# NNP-DWG-125-001-000_PG4_Schematic_Drawin.net
KiCad netlist of a schematic drawn in Altium Designer
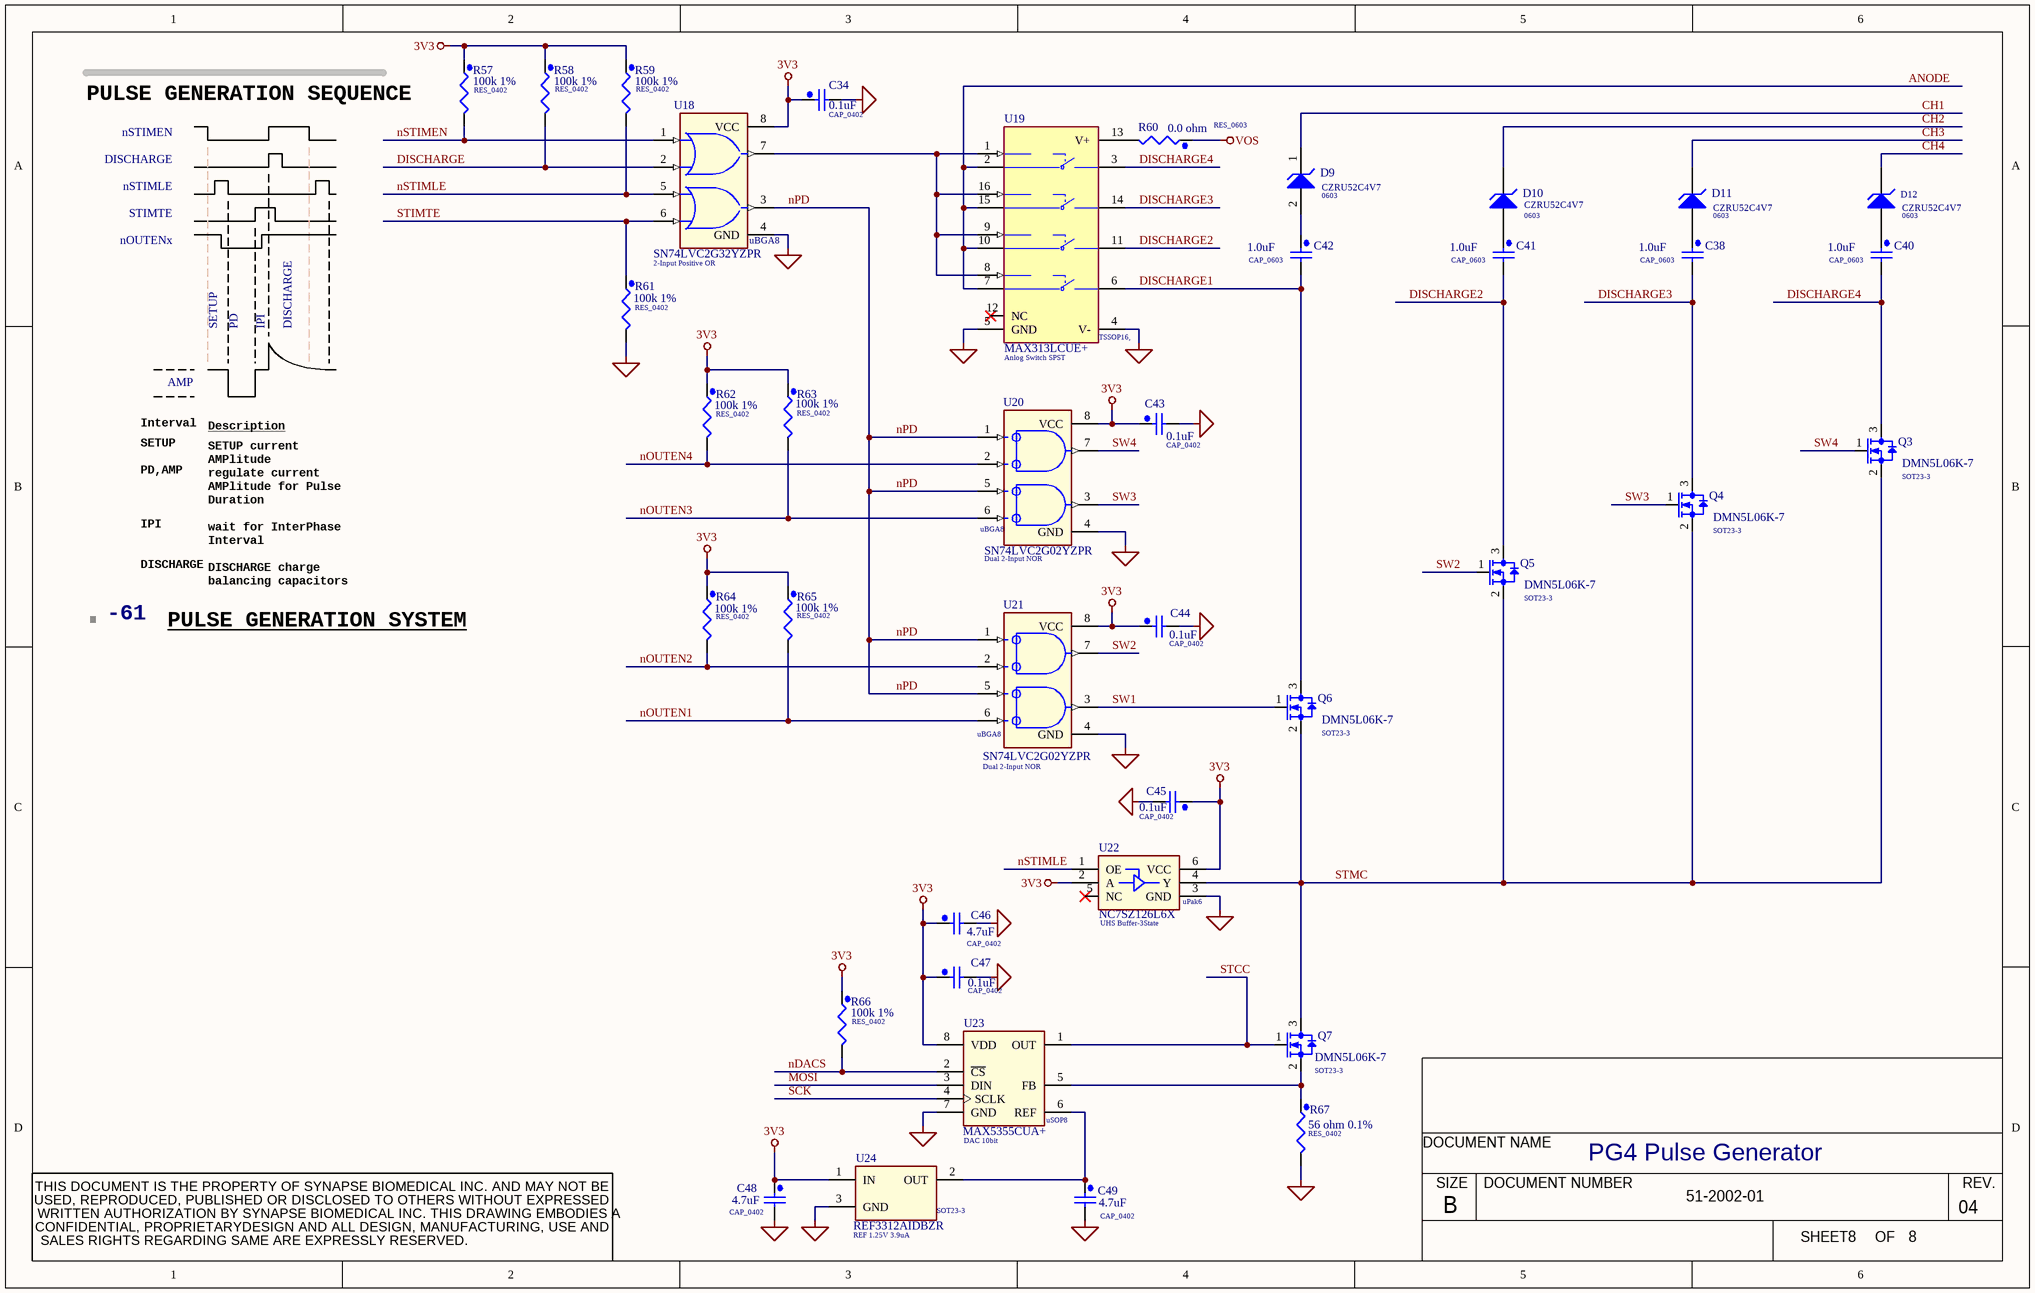
[diagram p0: NNP-DWG-125-001-000 PG4 Schematic Drawing Pg8.SchDoc]

(export (version "E")
  (design (tool "Eeschema 10.0.6"))
  (components
    (comp (ref "-61")
      (value "BOM_S1")
      (description "BOM item small graphic")
      (fields (field (name "XDESCRIPTION") "PULSE GENERATION SYSTEM"))
      (libsource (lib "BOM_sym") (part "BOM_S1"))
    )
    (comp (ref "C34")
      (value "0.1uF")
      (footprint "CAP_0402")
      (description "0.1uF, 16V, X7R, 0402, RoHS")
      (fields
        (field (name "MFR") "Murata Electronics North America")
        (field (name "PACKAGEDESCRIPTION") "CAP_0402")
        (field (name "MPN") "GRM155R71C104KA88D")
      )
      (libsource (lib "NNPS Integrated Parts") (part "GRM155R71C104KA88D"))
    )
    (comp (ref "C38")
      (value "1.0uF")
      (footprint "CAP_0603")
      (description "1uF, 50V, X5R, 10%, 0603, RoHS")
      (fields
        (field (name "MFR") "Murata Electronics North America")
        (field (name "PACKAGEDESCRIPTION") "CAP_0603")
        (field (name "MPN") "GRM188R61H105KAALD")
      )
      (libsource (lib "NNPS Integrated Parts") (part "UMK107BJ105KA-T"))
    )
    (comp (ref "C40")
      (value "1.0uF")
      (footprint "CAP_0603")
      (description "1uF, 50V, X5R, 10%, 0603, RoHS")
      (fields
        (field (name "MFR") "Murata Electronics North America")
        (field (name "PACKAGEDESCRIPTION") "CAP_0603")
        (field (name "MPN") "GRM188R61H105KAALD")
      )
      (libsource (lib "NNPS Integrated Parts") (part "UMK107BJ105KA-T"))
    )
    (comp (ref "C41")
      (value "1.0uF")
      (footprint "CAP_0603")
      (description "1uF, 50V, X5R, 10%, 0603, RoHS")
      (fields
        (field (name "MFR") "Murata Electronics North America")
        (field (name "PACKAGEDESCRIPTION") "CAP_0603")
        (field (name "MPN") "GRM188R61H105KAALD")
      )
      (libsource (lib "NNPS Integrated Parts") (part "UMK107BJ105KA-T"))
    )
    (comp (ref "C42")
      (value "1.0uF")
      (footprint "CAP_0603")
      (description "1uF, 50V, X5R, 10%, 0603, RoHS")
      (fields
        (field (name "MFR") "Murata Electronics North America")
        (field (name "PACKAGEDESCRIPTION") "CAP_0603")
        (field (name "MPN") "GRM188R61H105KAALD")
      )
      (libsource (lib "NNPS Integrated Parts") (part "UMK107BJ105KA-T"))
    )
    (comp (ref "C43")
      (value "0.1uF")
      (footprint "CAP_0402")
      (description "0.1uF, 16V, X7R, 0402, RoHS")
      (fields
        (field (name "MFR") "Murata Electronics North America")
        (field (name "PACKAGEDESCRIPTION") "CAP_0402")
        (field (name "MPN") "GRM155R71C104KA88D")
      )
      (libsource (lib "NNPS Integrated Parts") (part "GRM155R71C104KA88D"))
    )
    (comp (ref "C44")
      (value "0.1uF")
      (footprint "CAP_0402")
      (description "0.1uF, 16V, X7R, 0402, RoHS")
      (fields
        (field (name "MFR") "Murata Electronics North America")
        (field (name "PACKAGEDESCRIPTION") "CAP_0402")
        (field (name "MPN") "GRM155R71C104KA88D")
      )
      (libsource (lib "NNPS Integrated Parts") (part "GRM155R71C104KA88D"))
    )
    (comp (ref "C45")
      (value "0.1uF")
      (footprint "CAP_0402")
      (description "0.1uF, 16V, X7R, 0402, RoHS")
      (fields
        (field (name "MFR") "Murata Electronics North America")
        (field (name "PACKAGEDESCRIPTION") "CAP_0402")
        (field (name "MPN") "GRM155R71C104KA88D")
      )
      (libsource (lib "NNPS Integrated Parts") (part "GRM155R71C104KA88D"))
    )
    (comp (ref "C46")
      (value "4.7uF")
      (footprint "CAP_0402")
      (description "4.7uF, 6.3V, X5R, 20%, 0402, RoHS")
      (fields
        (field (name "MFR") "Murata Electronics North America")
        (field (name "PACKAGEDESCRIPTION") "CAP_0402")
        (field (name "MPN") "GRM155R60J475ME47D")
      )
      (libsource (lib "NNPS Integrated Parts") (part "ECJ-0EB0J475M"))
    )
    (comp (ref "C47")
      (value "0.1uF")
      (footprint "CAP_0402")
      (description "0.1uF, 16V, X7R, 0402, RoHS")
      (fields
        (field (name "MFR") "Murata Electronics North America")
        (field (name "PACKAGEDESCRIPTION") "CAP_0402")
        (field (name "MPN") "GRM155R71C104KA88D")
      )
      (libsource (lib "NNPS Integrated Parts") (part "GRM155R71C104KA88D"))
    )
    (comp (ref "C48")
      (value "4.7uF")
      (footprint "CAP_0402")
      (description "4.7uF, 6.3V, X5R, 20%, 0402, RoHS")
      (fields
        (field (name "MFR") "Murata Electronics North America")
        (field (name "PACKAGEDESCRIPTION") "CAP_0402")
        (field (name "MPN") "GRM155R60J475ME47D")
      )
      (libsource (lib "NNPS Integrated Parts") (part "ECJ-0EB0J475M"))
    )
    (comp (ref "C49")
      (value "4.7uF")
      (footprint "CAP_0402")
      (description "4.7uF, 6.3V, X5R, 20%, 0402, RoHS")
      (fields
        (field (name "MFR") "Murata Electronics North America")
        (field (name "PACKAGEDESCRIPTION") "CAP_0402")
        (field (name "MPN") "GRM155R60J475ME47D")
      )
      (libsource (lib "NNPS Integrated Parts") (part "ECJ-0EB0J475M"))
    )
    (comp (ref "D9")
      (value "Zener Diode, 15V, 150mW, 0603, RoHS")
      (footprint "DIODES_SOD-523FL")
      (description "Zener Diode, 4.7V, 150 mW, 0603, RoHS")
      (fields
        (field (name "MFR") "Comchip Technology")
        (field (name "PACKAGEDESCRIPTION") "0603")
        (field (name "MPN") "CZRU52C4V7")
      )
      (libsource (lib "Simulation Sources") (part "DFLZ15-7"))
    )
    (comp (ref "D10")
      (value "Zener Diode, 15V, 150mW, 0603, RoHS")
      (footprint "B0-0000-85-8 Rev 006-a Altium Source for PCB:DIODES_SOD-523FL")
      (description "Zener Diode, 4.7V, 150 mW, 0603, RoHS")
      (fields
        (field (name "MFR") "Comchip Technology")
        (field (name "PACKAGEDESCRIPTION") "0603")
        (field (name "MPN") "CZRU52C4V7")
      )
      (libsource (lib "NNPS Integrated Parts") (part "DFLZ15-7"))
    )
    (comp (ref "D11")
      (value "Zener Diode, 15V, 150mW, 0603, RoHS")
      (footprint "DIODES_SOD-523FL")
      (description "Zener Diode, 4.7V, 150 mW, 0603, RoHS")
      (fields
        (field (name "MFR") "Comchip Technology")
        (field (name "PACKAGEDESCRIPTION") "0603")
        (field (name "MPN") "CZRU52C4V7")
      )
      (libsource (lib "NNPS Integrated Parts") (part "DFLZ15-7"))
    )
    (comp (ref "D12")
      (value "Zener Diode, 15V, 150mW, 0603, RoHS")
      (footprint "DIODES_SOD-523FL")
      (description "Zener Diode, 4.7V, 150 mW, 0603, RoHS")
      (fields
        (field (name "MFR") "Comchip Technology")
        (field (name "PACKAGEDESCRIPTION") "0603")
        (field (name "MPN") "CZRU52C4V7")
      )
      (libsource (lib "NNPS Integrated Parts") (part "DFLZ15-7"))
    )
    (comp (ref "Q3")
      (value "DMN5L06K-7")
      (footprint "SOT23-3")
      (description "N-Channel MOSFET, 50V, 300mA, SOT23, RoHS")
      (fields
        (field (name "MFR") "Diodes Incorporated")
        (field (name "PACKAGEDESCRIPTION") "SOT23-3")
        (field (name "Comment") "M_50_300m_SOT23")
      )
      (libsource (lib "NNPS Integrated Parts") (part "DMN5L06K-7"))
    )
    (comp (ref "Q4")
      (value "DMN5L06K-7")
      (footprint "SOT23-3")
      (description "N-Channel MOSFET, 50V, 300mA, SOT23, RoHS")
      (fields
        (field (name "MFR") "Diodes Incorporated")
        (field (name "PACKAGEDESCRIPTION") "SOT23-3")
        (field (name "Comment") "M_50_300m_SOT23")
      )
      (libsource (lib "NNPS Integrated Parts") (part "DMN5L06K-7"))
    )
    (comp (ref "Q5")
      (value "DMN5L06K-7")
      (footprint "SOT23-3")
      (description "N-Channel MOSFET, 50V, 300mA, SOT23, RoHS")
      (fields
        (field (name "MFR") "Diodes Incorporated")
        (field (name "PACKAGEDESCRIPTION") "SOT23-3")
        (field (name "Comment") "M_50_300m_SOT23")
      )
      (libsource (lib "NNPS Integrated Parts") (part "DMN5L06K-7"))
    )
    (comp (ref "Q6")
      (value "DMN5L06K-7")
      (footprint "SOT23-3")
      (description "N-Channel MOSFET, 50V, 300mA, SOT23, RoHS")
      (fields
        (field (name "MFR") "Diodes Incorporated")
        (field (name "PACKAGEDESCRIPTION") "SOT23-3")
        (field (name "Comment") "M_50_300m_SOT23")
      )
      (libsource (lib "NNPS Integrated Parts") (part "DMN5L06K-7"))
    )
    (comp (ref "Q7")
      (value "DMN5L06K-7")
      (footprint "SOT23-3")
      (description "N-Channel MOSFET, 50V, 300mA, SOT23, RoHS")
      (fields
        (field (name "MFR") "Diodes Incorporated")
        (field (name "PACKAGEDESCRIPTION") "SOT23-3")
        (field (name "Comment") "M_50_300m_SOT23")
      )
      (libsource (lib "NNPS Integrated Parts") (part "DMN5L06K-7"))
    )
    (comp (ref "R57")
      (value "100k 1%")
      (footprint "RES_0402")
      (description "100k ohm, 1%, 1/16W, smd, 0402, RoHS")
      (fields
        (field (name "MFR") "Vishay Dale")
        (field (name "PACKAGEDESCRIPTION") "RES_0402")
        (field (name "MPN") "CRCW04025K10FKED")
      )
      (libsource (lib "NNPS Integrated Parts") (part "MCR01MZPF1003"))
    )
    (comp (ref "R58")
      (value "100k 1%")
      (footprint "RES_0402")
      (description "100k ohm, 1%, 1/16W, smd, 0402, RoHS")
      (fields
        (field (name "MFR") "Vishay Dale")
        (field (name "PACKAGEDESCRIPTION") "RES_0402")
        (field (name "MPN") "CRCW04025K10FKED")
      )
      (libsource (lib "NNPS Integrated Parts") (part "MCR01MZPF1003"))
    )
    (comp (ref "R59")
      (value "100k 1%")
      (footprint "RES_0402")
      (description "100k ohm, 1%, 1/16W, smd, 0402, RoHS")
      (fields
        (field (name "MFR") "Vishay Dale")
        (field (name "PACKAGEDESCRIPTION") "RES_0402")
        (field (name "MPN") "CRCW04025K10FKED")
      )
      (libsource (lib "NNPS Integrated Parts") (part "MCR01MZPF1003"))
    )
    (comp (ref "R60")
      (value "0.0 ohm")
      (footprint "RES_0603")
      (description "0.0 ohm, 1/10W, 0603, RoHS")
      (fields
        (field (name "MFR") "Vishay Dale")
        (field (name "PACKAGEDESCRIPTION") "RES_0603")
        (field (name "MPN") "MCR03ERTJ000")
      )
      (libsource (lib "NNPS Integrated Parts") (part "MCR03ERTJ000"))
    )
    (comp (ref "R61")
      (value "100k 1%")
      (footprint "RES_0402")
      (description "100k ohm, 1%, 1/16W, smd, 0402, RoHS")
      (fields
        (field (name "MFR") "Vishay Dale")
        (field (name "PACKAGEDESCRIPTION") "RES_0402")
        (field (name "MPN") "CRCW04025K10FKED")
      )
      (libsource (lib "NNPS Integrated Parts") (part "MCR01MZPF1003"))
    )
    (comp (ref "R62")
      (value "100k 1%")
      (footprint "RES_0402")
      (description "100k ohm, 1%, 1/16W, smd, 0402, RoHS")
      (fields
        (field (name "MFR") "Vishay Dale")
        (field (name "PACKAGEDESCRIPTION") "RES_0402")
        (field (name "MPN") "CRCW04025K10FKED")
      )
      (libsource (lib "NNPS Integrated Parts") (part "MCR01MZPF1003"))
    )
    (comp (ref "R63")
      (value "100k 1%")
      (footprint "RES_0402")
      (description "100k ohm, 1%, 1/16W, smd, 0402, RoHS")
      (fields
        (field (name "MFR") "Vishay Dale")
        (field (name "PACKAGEDESCRIPTION") "RES_0402")
        (field (name "MPN") "CRCW04025K10FKED")
      )
      (libsource (lib "NNPS Integrated Parts") (part "MCR01MZPF1003"))
    )
    (comp (ref "R64")
      (value "100k 1%")
      (footprint "RES_0402")
      (description "100k ohm, 1%, 1/16W, smd, 0402, RoHS")
      (fields
        (field (name "MFR") "Vishay Dale")
        (field (name "PACKAGEDESCRIPTION") "RES_0402")
        (field (name "MPN") "CRCW04025K10FKED")
      )
      (libsource (lib "NNPS Integrated Parts") (part "MCR01MZPF1003"))
    )
    (comp (ref "R65")
      (value "100k 1%")
      (footprint "RES_0402")
      (description "100k ohm, 1%, 1/16W, smd, 0402, RoHS")
      (fields
        (field (name "MFR") "Vishay Dale")
        (field (name "PACKAGEDESCRIPTION") "RES_0402")
        (field (name "MPN") "CRCW04025K10FKED")
      )
      (libsource (lib "NNPS Integrated Parts") (part "MCR01MZPF1003"))
    )
    (comp (ref "R66")
      (value "100k 1%")
      (footprint "RES_0402")
      (description "100k ohm, 1%, 1/16W, smd, 0402, RoHS")
      (fields
        (field (name "MFR") "Vishay Dale")
        (field (name "PACKAGEDESCRIPTION") "RES_0402")
        (field (name "MPN") "CRCW04025K10FKED")
      )
      (libsource (lib "NNPS Integrated Parts") (part "MCR01MZPF1003"))
    )
    (comp (ref "R67")
      (value "56 ohm 0.1%")
      (footprint "RES_0402")
      (description "56 ohm, 0.1%, 1/16W, 0402, RoHS")
      (fields
        (field (name "MFR") "Vishay Dale")
        (field (name "PACKAGEDESCRIPTION") "RES_0402")
        (field (name "MPN") "CRCW040256R0FKED")
      )
      (libsource (lib "NNPS Integrated Parts") (part "RG1005P-560-B-T5"))
    )
    (comp (ref "U18")
      (value "2-Input Positive OR")
      (footprint "DSBGA-8-YZP")
      (description "2-Input Positive OR, 1.65-5.5V,  uBGA8, RoHS")
      (fields
        (field (name "MFR") "Texas Instruments")
        (field (name "PACKAGEDESCRIPTION") "uBGA8")
        (field (name "MPN") "SN74LVC2G32YZPR")
      )
      (libsource (lib "NNPS Integrated Parts") (part "SN74LVC2G32YEA"))
    )
    (comp (ref "U19")
      (value "Anlog Switch SPST")
      (footprint "TSSOP16")
      (description "Analog Switch, 10ohm, QUAD SPST, TSSOP16, RoHS")
      (fields
        (field (name "PACKAGEDESCRIPTION") "TSSOP16,")
        (field (name "MFR") "Maxim Integrated")
        (field (name "MPN") "MAX313LCUE+")
      )
      (libsource (lib "NNPS Integrated Parts") (part "MAX313LCUE"))
    )
    (comp (ref "U20")
      (value "Dual 2-Input NOR")
      (footprint "DSBGA-8-YZP")
      (description "Dual 2-Input NOR, 1.65-5.5V, uBGA8, RoHS")
      (fields
        (field (name "MFR") "Texas Instruments")
        (field (name "PACKAGEDESCRIPTION") "uBGA8")
        (field (name "MPN") "SN74LVC2G02YZPR")
      )
      (libsource (lib "NNPS Integrated Parts") (part "SN74LVC2G02YEA"))
    )
    (comp (ref "U21")
      (value "Dual 2-Input NOR")
      (footprint "DSBGA-8-YZP")
      (description "Dual 2-Input NOR, 1.65-5.5V, uBGA8, RoHS")
      (fields
        (field (name "MFR") "Texas Instruments")
        (field (name "PACKAGEDESCRIPTION") "uBGA8")
        (field (name "MPN") "SN74LVC2G02YZPR")
      )
      (libsource (lib "NNPS Integrated Parts") (part "SN74LVC2G02YEA"))
    )
    (comp (ref "U22")
      (value "UHS Buffer-3State")
      (footprint "uPak6")
      (description "UHS Buffer Tri-State, uPAK6, RoHS")
      (fields
        (field (name "MFR") "Fairchild Semiconductor")
        (field (name "PACKAGEDESCRIPTION") "uPak6")
        (field (name "MPN") "NC7SZ126L6X")
      )
      (libsource (lib "NNPS Integrated Parts") (part "NC7SZ126L6X"))
    )
    (comp (ref "U23")
      (value "DAC 10bit")
      (footprint "uSOP-8L")
      (description "DAC 10bit, uSOP8, RoHS")
      (fields
        (field (name "PACKAGEDESCRIPTION") "uSOP8")
        (field (name "MFR") "Maxim Integrated")
        (field (name "MPN") "MAX5355CUA+")
      )
      (libsource (lib "NNPS Integrated Parts") (part "MAX5355CUA+"))
    )
    (comp (ref "U24")
      (value "REF 1.25V 3.9uA")
      (footprint "SOT23-3")
      (description "REF 1.25V, 3.9uA, SOT23-3, RoHS")
      (fields
        (field (name "PACKAGEDESCRIPTION") "SOT23-3")
        (field (name "MFR") "Texas Instruments")
        (field (name "MPN") "REF3312AIDBZR")
      )
      (libsource (lib "NNPS Integrated Parts") (part "REF3312AIDCK"))
    )
  )
  (nets
    (net (code "1") (name "/ANODE") (class "Default")
      (node (ref "U19") (pin "10") (pinfunction "COM3_10") (pintype "passive"))
      (node (ref "U19") (pin "15") (pinfunction "COM2_15") (pintype "passive"))
      (node (ref "U19") (pin "2") (pinfunction "COM1_2") (pintype "passive"))
      (node (ref "U19") (pin "7") (pinfunction "COM4_7") (pintype "passive"))
    )
    (net (code "2") (name "/CH1") (class "Default")
      (node (ref "D9") (pin "1") (pinfunction "1_1") (pintype "passive"))
    )
    (net (code "3") (name "/CH2") (class "Default")
      (node (ref "D10") (pin "1") (pinfunction "C_1") (pintype "passive"))
    )
    (net (code "4") (name "/CH3") (class "Default")
      (node (ref "D11") (pin "1") (pinfunction "C_1") (pintype "passive"))
    )
    (net (code "5") (name "/CH4") (class "Default")
      (node (ref "D12") (pin "1") (pinfunction "C_1") (pintype "passive"))
    )
    (net (code "6") (name "/DISCHARGE") (class "Default")
      (node (ref "R58") (pin "2") (pinfunction "2_2") (pintype "passive"))
      (node (ref "U18") (pin "2") (pinfunction "1B_2") (pintype "input"))
    )
    (net (code "7") (name "/DISCHARGE1") (class "Default")
      (node (ref "C42") (pin "2") (pinfunction "2_2") (pintype "passive"))
      (node (ref "Q6") (pin "3") (pinfunction "D_3") (pintype "passive"))
      (node (ref "U19") (pin "6") (pinfunction "NO4_6") (pintype "passive"))
    )
    (net (code "8") (name "/DISCHARGE2") (class "Default")
      (node (ref "C41") (pin "2") (pinfunction "2_2") (pintype "passive"))
      (node (ref "Q5") (pin "3") (pinfunction "D_3") (pintype "passive"))
      (node (ref "U19") (pin "11") (pinfunction "NO3_11") (pintype "passive"))
    )
    (net (code "9") (name "/DISCHARGE3") (class "Default")
      (node (ref "C38") (pin "2") (pinfunction "2_2") (pintype "passive"))
      (node (ref "Q4") (pin "3") (pinfunction "D_3") (pintype "passive"))
      (node (ref "U19") (pin "14") (pinfunction "NO2_14") (pintype "passive"))
    )
    (net (code "10") (name "/DISCHARGE4") (class "Default")
      (node (ref "C40") (pin "2") (pinfunction "2_2") (pintype "passive"))
      (node (ref "Q3") (pin "3") (pinfunction "D_3") (pintype "passive"))
      (node (ref "U19") (pin "3") (pinfunction "NO1_3") (pintype "passive"))
    )
    (net (code "11") (name "/MOSI") (class "Default")
      (node (ref "U23") (pin "3") (pinfunction "DIN_3") (pintype "passive"))
    )
    (net (code "12") (name "/SCK") (class "Default")
      (node (ref "U23") (pin "4") (pinfunction "SCLK_4") (pintype "passive"))
    )
    (net (code "13") (name "/STCC") (class "Default")
      (node (ref "Q7") (pin "1") (pinfunction "G_1") (pintype "passive"))
      (node (ref "U23") (pin "1") (pinfunction "OUT_1") (pintype "passive"))
    )
    (net (code "14") (name "/STIMTE") (class "Default")
      (node (ref "R61") (pin "1") (pinfunction "1_1") (pintype "passive"))
      (node (ref "U18") (pin "6") (pinfunction "2B_6") (pintype "input"))
    )
    (net (code "15") (name "/STMC") (class "Default")
      (node (ref "Q3") (pin "2") (pinfunction "S_2") (pintype "passive"))
      (node (ref "Q4") (pin "2") (pinfunction "S_2") (pintype "passive"))
      (node (ref "Q5") (pin "2") (pinfunction "S_2") (pintype "passive"))
      (node (ref "Q6") (pin "2") (pinfunction "S_2") (pintype "passive"))
      (node (ref "Q7") (pin "3") (pinfunction "D_3") (pintype "passive"))
      (node (ref "U22") (pin "4") (pinfunction "Y_4") (pintype "passive"))
    )
    (net (code "16") (name "/SW1") (class "Default")
      (node (ref "Q6") (pin "1") (pinfunction "G_1") (pintype "passive"))
      (node (ref "U21") (pin "3") (pinfunction "2Y_3") (pintype "output"))
    )
    (net (code "17") (name "/SW2") (class "Default")
      (node (ref "Q5") (pin "1") (pinfunction "G_1") (pintype "passive"))
      (node (ref "U21") (pin "7") (pinfunction "Y_7") (pintype "output"))
    )
    (net (code "18") (name "/SW3") (class "Default")
      (node (ref "Q4") (pin "1") (pinfunction "G_1") (pintype "passive"))
      (node (ref "U20") (pin "3") (pinfunction "2Y_3") (pintype "output"))
    )
    (net (code "19") (name "/SW4") (class "Default")
      (node (ref "Q3") (pin "1") (pinfunction "G_1") (pintype "passive"))
      (node (ref "U20") (pin "7") (pinfunction "Y_7") (pintype "output"))
    )
    (net (code "20") (name "/nDACS") (class "Default")
      (node (ref "R66") (pin "2") (pinfunction "2_2") (pintype "passive"))
      (node (ref "U23") (pin "2") (pinfunction "~{CS}_2") (pintype "passive"))
    )
    (net (code "21") (name "/nOUTEN1") (class "Default")
      (node (ref "R65") (pin "2") (pinfunction "2_2") (pintype "passive"))
      (node (ref "U21") (pin "6") (pinfunction "2B_6") (pintype "input"))
    )
    (net (code "22") (name "/nOUTEN2") (class "Default")
      (node (ref "R64") (pin "2") (pinfunction "2_2") (pintype "passive"))
      (node (ref "U21") (pin "2") (pinfunction "1B_2") (pintype "input"))
    )
    (net (code "23") (name "/nOUTEN3") (class "Default")
      (node (ref "R63") (pin "2") (pinfunction "2_2") (pintype "passive"))
      (node (ref "U20") (pin "6") (pinfunction "2B_6") (pintype "input"))
    )
    (net (code "24") (name "/nOUTEN4") (class "Default")
      (node (ref "R62") (pin "2") (pinfunction "2_2") (pintype "passive"))
      (node (ref "U20") (pin "2") (pinfunction "1B_2") (pintype "input"))
    )
    (net (code "25") (name "/nPD") (class "Default")
      (node (ref "U18") (pin "3") (pinfunction "2Y_3") (pintype "output"))
      (node (ref "U20") (pin "1") (pinfunction "1A_1") (pintype "input"))
      (node (ref "U20") (pin "5") (pinfunction "2A_5") (pintype "input"))
      (node (ref "U21") (pin "1") (pinfunction "1A_1") (pintype "input"))
      (node (ref "U21") (pin "5") (pinfunction "2A_5") (pintype "input"))
    )
    (net (code "26") (name "/nSTIMEN") (class "Default")
      (node (ref "R57") (pin "2") (pinfunction "2_2") (pintype "passive"))
      (node (ref "U18") (pin "1") (pinfunction "1A_1") (pintype "input"))
    )
    (net (code "27") (name "/nSTIMLE") (class "Default")
      (node (ref "R59") (pin "2") (pinfunction "2_2") (pintype "passive"))
      (node (ref "U18") (pin "5") (pinfunction "2A_5") (pintype "input"))
      (node (ref "U22") (pin "1") (pinfunction "OE_1") (pintype "passive"))
    )
    (net (code "28") (name "3V3") (class "Default")
      (node (ref "C34") (pin "1") (pinfunction "1_1") (pintype "passive"))
      (node (ref "C43") (pin "1") (pinfunction "1_1") (pintype "passive"))
      (node (ref "C44") (pin "1") (pinfunction "1_1") (pintype "passive"))
      (node (ref "C45") (pin "1") (pinfunction "1_1") (pintype "passive"))
      (node (ref "C46") (pin "1") (pinfunction "1_1") (pintype "passive"))
      (node (ref "C47") (pin "1") (pinfunction "1_1") (pintype "passive"))
      (node (ref "C48") (pin "1") (pinfunction "1_1") (pintype "passive"))
      (node (ref "R57") (pin "1") (pinfunction "1_1") (pintype "passive"))
      (node (ref "R58") (pin "1") (pinfunction "1_1") (pintype "passive"))
      (node (ref "R59") (pin "1") (pinfunction "1_1") (pintype "passive"))
      (node (ref "R62") (pin "1") (pinfunction "1_1") (pintype "passive"))
      (node (ref "R63") (pin "1") (pinfunction "1_1") (pintype "passive"))
      (node (ref "R64") (pin "1") (pinfunction "1_1") (pintype "passive"))
      (node (ref "R65") (pin "1") (pinfunction "1_1") (pintype "passive"))
      (node (ref "R66") (pin "1") (pinfunction "1_1") (pintype "passive"))
      (node (ref "U18") (pin "8") (pinfunction "VCC_8") (pintype "power_in"))
      (node (ref "U20") (pin "8") (pinfunction "VCC_8") (pintype "power_in"))
      (node (ref "U21") (pin "8") (pinfunction "VCC_8") (pintype "power_in"))
      (node (ref "U22") (pin "2") (pinfunction "A_2") (pintype "passive"))
      (node (ref "U22") (pin "6") (pinfunction "VCC_6") (pintype "passive"))
      (node (ref "U23") (pin "8") (pinfunction "VDD_8") (pintype "passive"))
      (node (ref "U24") (pin "1") (pinfunction "IN_1") (pintype "power_in"))
    )
    (net (code "29") (name "GND") (class "Default")
      (node (ref "C34") (pin "2") (pinfunction "2_2") (pintype "passive"))
      (node (ref "C43") (pin "2") (pinfunction "2_2") (pintype "passive"))
      (node (ref "C44") (pin "2") (pinfunction "2_2") (pintype "passive"))
      (node (ref "C45") (pin "2") (pinfunction "2_2") (pintype "passive"))
      (node (ref "C46") (pin "2") (pinfunction "2_2") (pintype "passive"))
      (node (ref "C47") (pin "2") (pinfunction "2_2") (pintype "passive"))
      (node (ref "C48") (pin "2") (pinfunction "2_2") (pintype "passive"))
      (node (ref "C49") (pin "2") (pinfunction "2_2") (pintype "passive"))
      (node (ref "R61") (pin "2") (pinfunction "2_2") (pintype "passive"))
      (node (ref "R67") (pin "2") (pinfunction "2_2") (pintype "passive"))
      (node (ref "U18") (pin "4") (pinfunction "GND_4") (pintype "power_in"))
      (node (ref "U19") (pin "4") (pinfunction "V-_4") (pintype "power_in"))
      (node (ref "U19") (pin "5") (pinfunction "GND_5") (pintype "power_in"))
      (node (ref "U20") (pin "4") (pinfunction "GND_4") (pintype "power_in"))
      (node (ref "U21") (pin "4") (pinfunction "GND_4") (pintype "power_in"))
      (node (ref "U22") (pin "3") (pinfunction "GND_3") (pintype "passive"))
      (node (ref "U23") (pin "7") (pinfunction "GND_7") (pintype "passive"))
      (node (ref "U24") (pin "3") (pinfunction "GND_3") (pintype "power_in"))
    )
    (net (code "30") (name "Net-(D9-A)") (class "Default")
      (node (ref "C42") (pin "1") (pinfunction "1_1") (pintype "passive"))
      (node (ref "D9") (pin "2") (pinfunction "A_2") (pintype "passive"))
    )
    (net (code "31") (name "Net-(D10-A)") (class "Default")
      (node (ref "C41") (pin "1") (pinfunction "1_1") (pintype "passive"))
      (node (ref "D10") (pin "2") (pinfunction "A_2") (pintype "passive"))
    )
    (net (code "32") (name "Net-(D11-A)") (class "Default")
      (node (ref "C38") (pin "1") (pinfunction "1_1") (pintype "passive"))
      (node (ref "D11") (pin "2") (pinfunction "A_2") (pintype "passive"))
    )
    (net (code "33") (name "Net-(D12-A)") (class "Default")
      (node (ref "C40") (pin "1") (pinfunction "1_1") (pintype "passive"))
      (node (ref "D12") (pin "2") (pinfunction "A_2") (pintype "passive"))
    )
    (net (code "34") (name "Net-(Q7-S)") (class "Default")
      (node (ref "Q7") (pin "2") (pinfunction "S_2") (pintype "passive"))
      (node (ref "R67") (pin "1") (pinfunction "1_1") (pintype "passive"))
      (node (ref "U23") (pin "5") (pinfunction "FB_5") (pintype "passive"))
    )
    (net (code "35") (name "Net-(U18-Y)") (class "Default")
      (node (ref "U18") (pin "7") (pinfunction "Y_7") (pintype "output"))
      (node (ref "U19") (pin "1") (pinfunction "IN1_1") (pintype "input"))
      (node (ref "U19") (pin "16") (pinfunction "IN2_16") (pintype "input"))
      (node (ref "U19") (pin "8") (pinfunction "IN_4_8") (pintype "input"))
      (node (ref "U19") (pin "9") (pinfunction "IN3_9") (pintype "input"))
    )
    (net (code "36") (name "Net-(U19-V+)") (class "Default")
      (node (ref "R60") (pin "2") (pinfunction "2_2") (pintype "passive"))
      (node (ref "U19") (pin "13") (pinfunction "V+_13") (pintype "power_in"))
    )
    (net (code "37") (name "Net-(U23-REF)") (class "Default")
      (node (ref "C49") (pin "1") (pinfunction "1_1") (pintype "passive"))
      (node (ref "U23") (pin "6") (pinfunction "REF_6") (pintype "passive"))
      (node (ref "U24") (pin "2") (pinfunction "OUT_2") (pintype "passive"))
    )
    (net (code "38") (name "VOS") (class "Default")
      (node (ref "R60") (pin "1") (pinfunction "1_1") (pintype "passive"))
    )
    (net (code "39") (name "unconnected-(U19-NC-Pad12)") (class "Default")
      (node (ref "U19") (pin "12") (pinfunction "NC_12") (pintype "power_in+no_connect"))
    )
    (net (code "40") (name "unconnected-(U22-NC-Pad5)") (class "Default")
      (node (ref "U22") (pin "5") (pinfunction "NC_5") (pintype "passive+no_connect"))
    )
  )
)
